# ProtoMole5.net
KiCad netlist of a schematic drawn in EAGLE
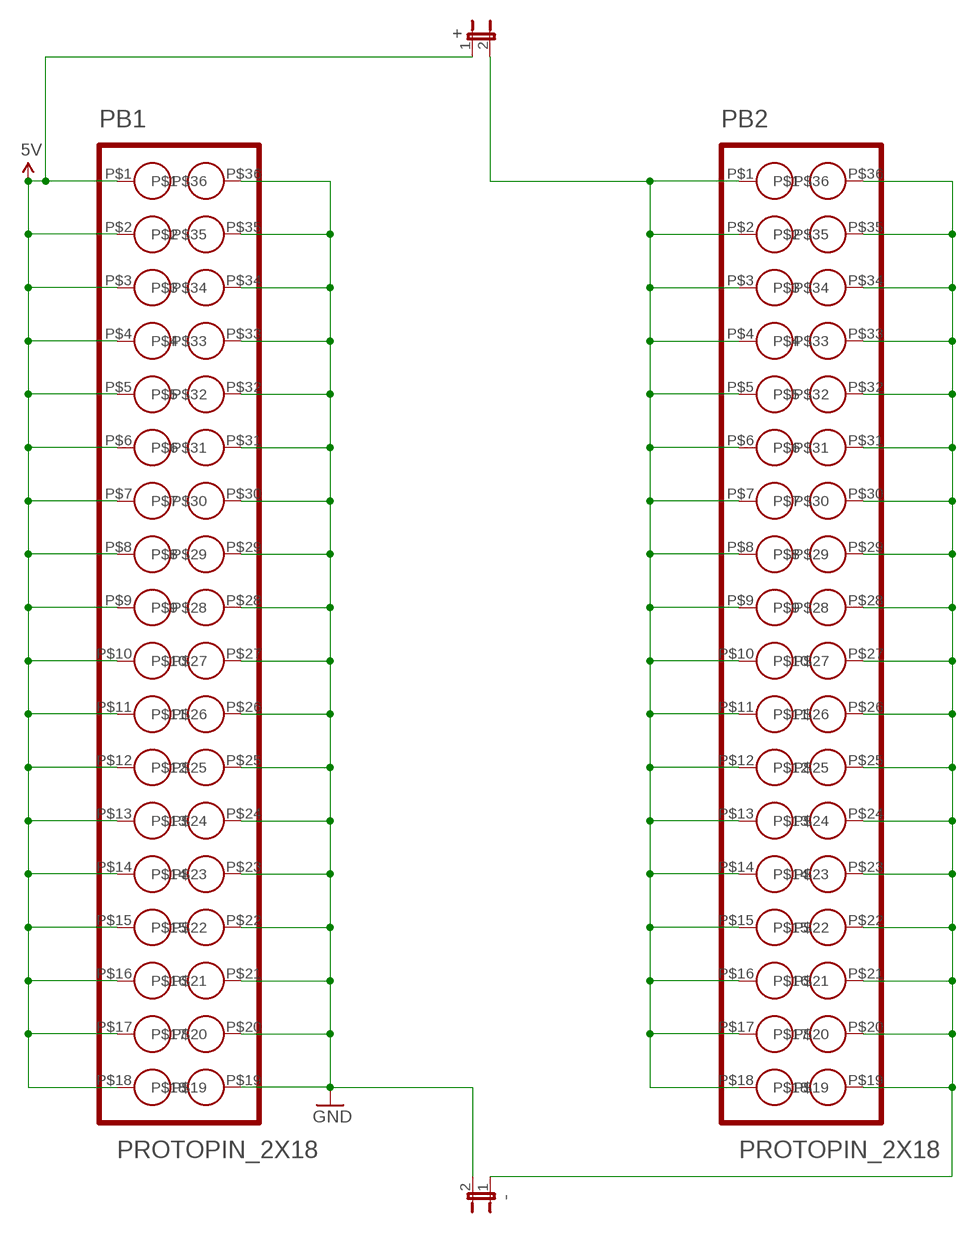
[diagram p0: schematic, sheet 1]

(export (version "E")
  (design (tool "Eeschema 10.0.6"))
  (components
    (comp (ref "+")
      (value "JUMPER-2SMD-NO-NS")
      (footprint "eagle-import:SJ_2S-NO-NS")
      (libsource (lib "eagle-import") (part "JUMPER-2SMD-NO-NS"))
    )
    (comp (ref "-")
      (value "JUMPER-2SMD-NO-NS")
      (footprint "eagle-import:SJ_2S-NO-NS")
      (libsource (lib "eagle-import") (part "JUMPER-2SMD-NO-NS"))
    )
    (comp (ref "PB1")
      (value "PROTOPIN_2X18")
      (footprint "eagle-import:2X18_PINHEADER")
      (libsource (lib "eagle-import") (part "PROTOPIN_2X18"))
    )
    (comp (ref "PB2")
      (value "PROTOPIN_2X18")
      (footprint "eagle-import:2X18_PINHEADER")
      (libsource (lib "eagle-import") (part "PROTOPIN_2X18"))
    )
  )
  (nets
    (net (code "1") (name "5V") (class "Default")
      (node (ref "+") (pin "1") (pinfunction "1_1") (pintype "passive"))
      (node (ref "PB1") (pin "P$1") (pinfunction "P$1_P$1") (pintype "passive"))
      (node (ref "PB1") (pin "P$10") (pinfunction "P$10_P$10") (pintype "passive"))
      (node (ref "PB1") (pin "P$11") (pinfunction "P$11_P$11") (pintype "passive"))
      (node (ref "PB1") (pin "P$12") (pinfunction "P$12_P$12") (pintype "passive"))
      (node (ref "PB1") (pin "P$13") (pinfunction "P$13_P$13") (pintype "passive"))
      (node (ref "PB1") (pin "P$14") (pinfunction "P$14_P$14") (pintype "passive"))
      (node (ref "PB1") (pin "P$15") (pinfunction "P$15_P$15") (pintype "passive"))
      (node (ref "PB1") (pin "P$16") (pinfunction "P$16_P$16") (pintype "passive"))
      (node (ref "PB1") (pin "P$17") (pinfunction "P$17_P$17") (pintype "passive"))
      (node (ref "PB1") (pin "P$18") (pinfunction "P$18_P$18") (pintype "passive"))
      (node (ref "PB1") (pin "P$2") (pinfunction "P$2_P$2") (pintype "passive"))
      (node (ref "PB1") (pin "P$3") (pinfunction "P$3_P$3") (pintype "passive"))
      (node (ref "PB1") (pin "P$4") (pinfunction "P$4_P$4") (pintype "passive"))
      (node (ref "PB1") (pin "P$5") (pinfunction "P$5_P$5") (pintype "passive"))
      (node (ref "PB1") (pin "P$6") (pinfunction "P$6_P$6") (pintype "passive"))
      (node (ref "PB1") (pin "P$7") (pinfunction "P$7_P$7") (pintype "passive"))
      (node (ref "PB1") (pin "P$8") (pinfunction "P$8_P$8") (pintype "passive"))
      (node (ref "PB1") (pin "P$9") (pinfunction "P$9_P$9") (pintype "passive"))
    )
    (net (code "2") (name "GND") (class "Default")
      (node (ref "-") (pin "2") (pinfunction "2_2") (pintype "passive"))
      (node (ref "PB1") (pin "P$19") (pinfunction "P$19_P$19") (pintype "passive"))
      (node (ref "PB1") (pin "P$20") (pinfunction "P$20_P$20") (pintype "passive"))
      (node (ref "PB1") (pin "P$21") (pinfunction "P$21_P$21") (pintype "passive"))
      (node (ref "PB1") (pin "P$22") (pinfunction "P$22_P$22") (pintype "passive"))
      (node (ref "PB1") (pin "P$23") (pinfunction "P$23_P$23") (pintype "passive"))
      (node (ref "PB1") (pin "P$24") (pinfunction "P$24_P$24") (pintype "passive"))
      (node (ref "PB1") (pin "P$25") (pinfunction "P$25_P$25") (pintype "passive"))
      (node (ref "PB1") (pin "P$26") (pinfunction "P$26_P$26") (pintype "passive"))
      (node (ref "PB1") (pin "P$27") (pinfunction "P$27_P$27") (pintype "passive"))
      (node (ref "PB1") (pin "P$28") (pinfunction "P$28_P$28") (pintype "passive"))
      (node (ref "PB1") (pin "P$29") (pinfunction "P$29_P$29") (pintype "passive"))
      (node (ref "PB1") (pin "P$30") (pinfunction "P$30_P$30") (pintype "passive"))
      (node (ref "PB1") (pin "P$31") (pinfunction "P$31_P$31") (pintype "passive"))
      (node (ref "PB1") (pin "P$32") (pinfunction "P$32_P$32") (pintype "passive"))
      (node (ref "PB1") (pin "P$33") (pinfunction "P$33_P$33") (pintype "passive"))
      (node (ref "PB1") (pin "P$34") (pinfunction "P$34_P$34") (pintype "passive"))
      (node (ref "PB1") (pin "P$35") (pinfunction "P$35_P$35") (pintype "passive"))
      (node (ref "PB1") (pin "P$36") (pinfunction "P$36_P$36") (pintype "passive"))
    )
    (net (code "3") (name "Net-(+-Pad2)") (class "Default")
      (node (ref "+") (pin "2") (pinfunction "2_2") (pintype "passive"))
      (node (ref "PB2") (pin "P$1") (pinfunction "P$1_P$1") (pintype "passive"))
      (node (ref "PB2") (pin "P$10") (pinfunction "P$10_P$10") (pintype "passive"))
      (node (ref "PB2") (pin "P$11") (pinfunction "P$11_P$11") (pintype "passive"))
      (node (ref "PB2") (pin "P$12") (pinfunction "P$12_P$12") (pintype "passive"))
      (node (ref "PB2") (pin "P$13") (pinfunction "P$13_P$13") (pintype "passive"))
      (node (ref "PB2") (pin "P$14") (pinfunction "P$14_P$14") (pintype "passive"))
      (node (ref "PB2") (pin "P$15") (pinfunction "P$15_P$15") (pintype "passive"))
      (node (ref "PB2") (pin "P$16") (pinfunction "P$16_P$16") (pintype "passive"))
      (node (ref "PB2") (pin "P$17") (pinfunction "P$17_P$17") (pintype "passive"))
      (node (ref "PB2") (pin "P$18") (pinfunction "P$18_P$18") (pintype "passive"))
      (node (ref "PB2") (pin "P$2") (pinfunction "P$2_P$2") (pintype "passive"))
      (node (ref "PB2") (pin "P$3") (pinfunction "P$3_P$3") (pintype "passive"))
      (node (ref "PB2") (pin "P$4") (pinfunction "P$4_P$4") (pintype "passive"))
      (node (ref "PB2") (pin "P$5") (pinfunction "P$5_P$5") (pintype "passive"))
      (node (ref "PB2") (pin "P$6") (pinfunction "P$6_P$6") (pintype "passive"))
      (node (ref "PB2") (pin "P$7") (pinfunction "P$7_P$7") (pintype "passive"))
      (node (ref "PB2") (pin "P$8") (pinfunction "P$8_P$8") (pintype "passive"))
      (node (ref "PB2") (pin "P$9") (pinfunction "P$9_P$9") (pintype "passive"))
    )
    (net (code "4") (name "Net-(--Pad1)") (class "Default")
      (node (ref "-") (pin "1") (pinfunction "1_1") (pintype "passive"))
      (node (ref "PB2") (pin "P$19") (pinfunction "P$19_P$19") (pintype "passive"))
      (node (ref "PB2") (pin "P$20") (pinfunction "P$20_P$20") (pintype "passive"))
      (node (ref "PB2") (pin "P$21") (pinfunction "P$21_P$21") (pintype "passive"))
      (node (ref "PB2") (pin "P$22") (pinfunction "P$22_P$22") (pintype "passive"))
      (node (ref "PB2") (pin "P$23") (pinfunction "P$23_P$23") (pintype "passive"))
      (node (ref "PB2") (pin "P$24") (pinfunction "P$24_P$24") (pintype "passive"))
      (node (ref "PB2") (pin "P$25") (pinfunction "P$25_P$25") (pintype "passive"))
      (node (ref "PB2") (pin "P$26") (pinfunction "P$26_P$26") (pintype "passive"))
      (node (ref "PB2") (pin "P$27") (pinfunction "P$27_P$27") (pintype "passive"))
      (node (ref "PB2") (pin "P$28") (pinfunction "P$28_P$28") (pintype "passive"))
      (node (ref "PB2") (pin "P$29") (pinfunction "P$29_P$29") (pintype "passive"))
      (node (ref "PB2") (pin "P$30") (pinfunction "P$30_P$30") (pintype "passive"))
      (node (ref "PB2") (pin "P$31") (pinfunction "P$31_P$31") (pintype "passive"))
      (node (ref "PB2") (pin "P$32") (pinfunction "P$32_P$32") (pintype "passive"))
      (node (ref "PB2") (pin "P$33") (pinfunction "P$33_P$33") (pintype "passive"))
      (node (ref "PB2") (pin "P$34") (pinfunction "P$34_P$34") (pintype "passive"))
      (node (ref "PB2") (pin "P$35") (pinfunction "P$35_P$35") (pintype "passive"))
      (node (ref "PB2") (pin "P$36") (pinfunction "P$36_P$36") (pintype "passive"))
    )
  )
)
